# FATSC-DevKit_v10.net
KiCad netlist of a schematic drawn in EAGLE
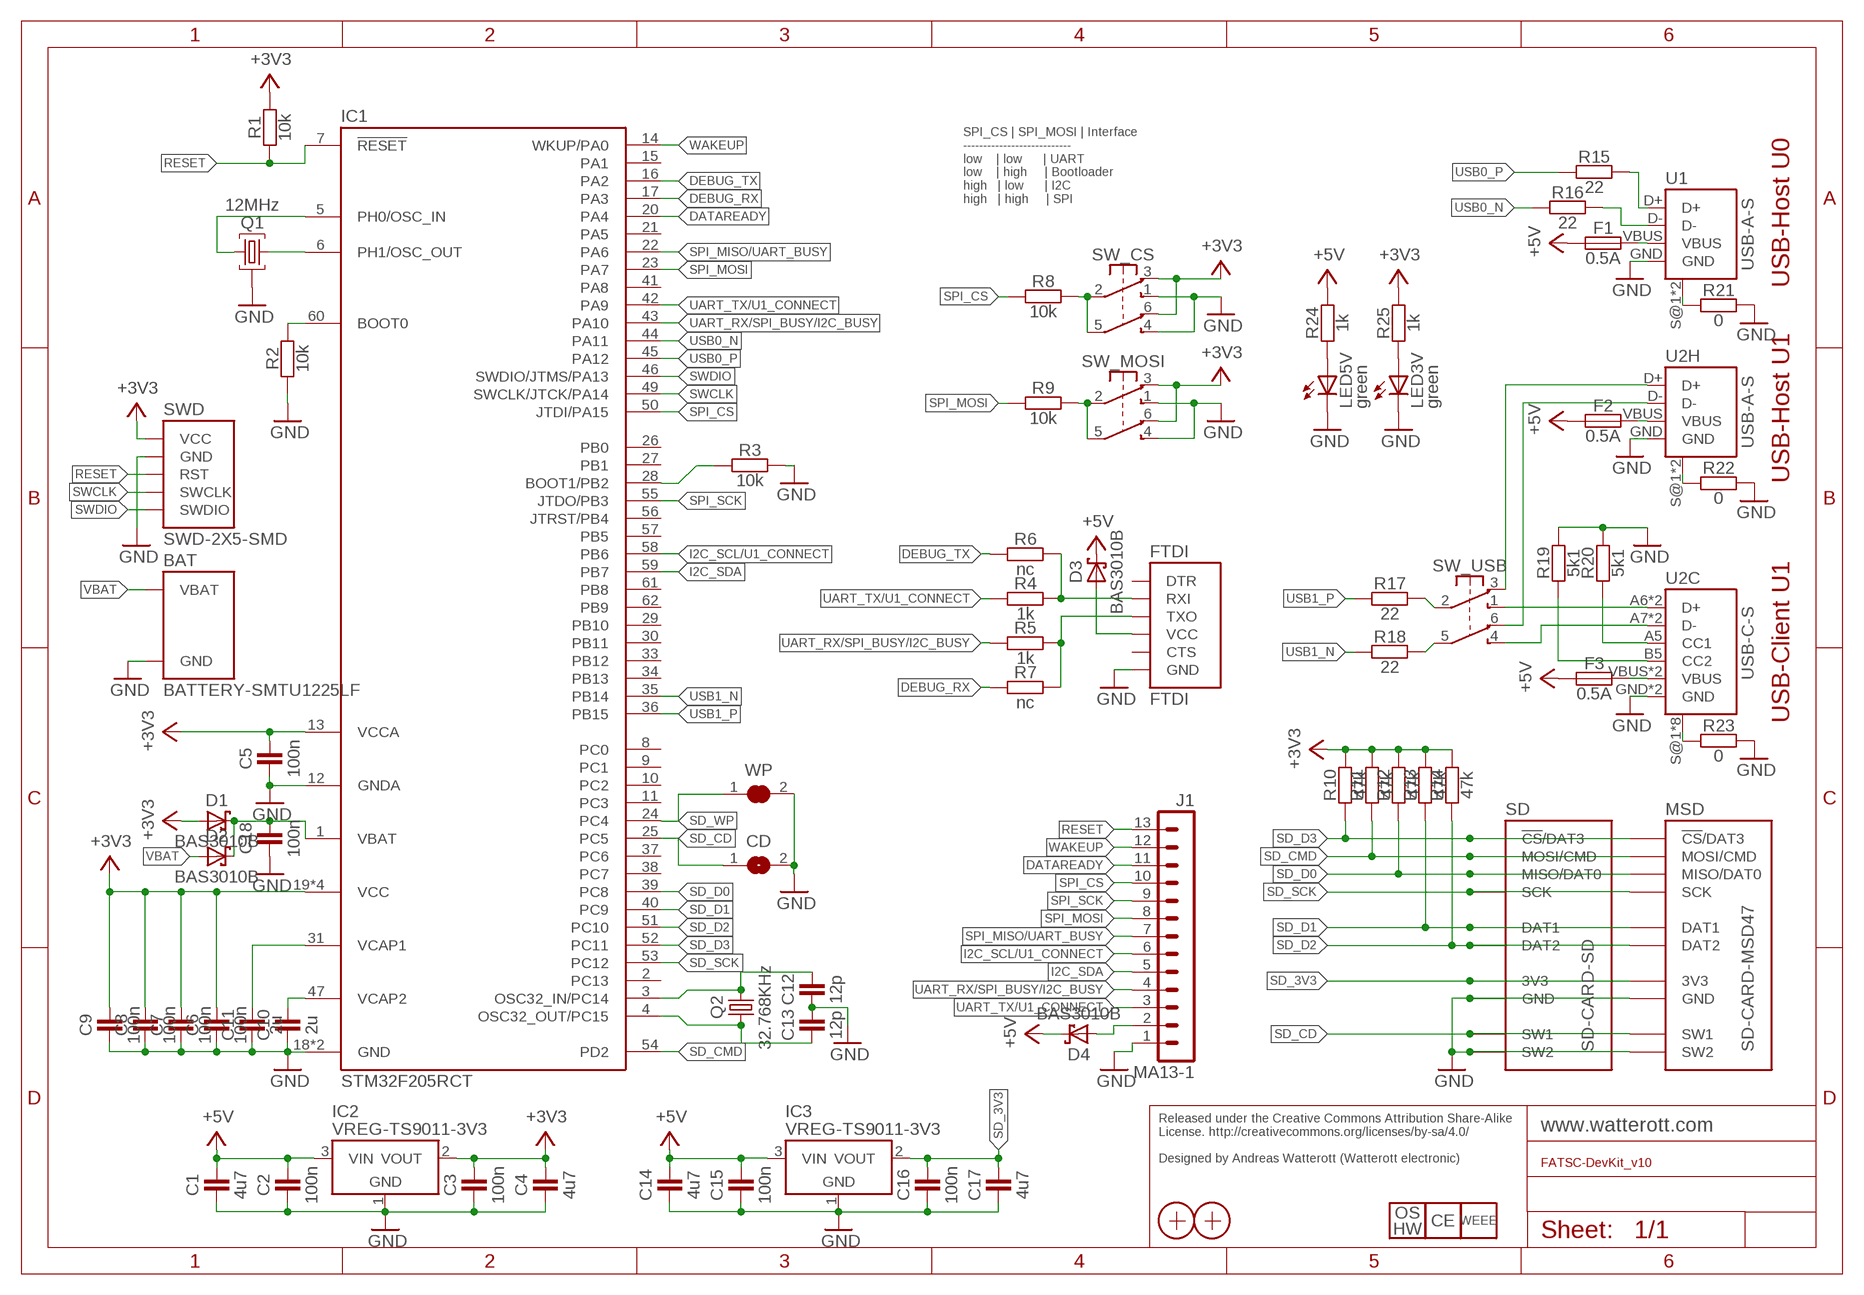
[diagram p0: schematic, sheet 1]

(export (version "E")
  (design (tool "Eeschema 10.0.6"))
  (components
    (comp (ref "BAT")
      (value "BATTERY-SMTU1225LF")
      (footprint "eagle-import:BAT-SMTU1225LF")
      (libsource (lib "eagle-import") (part "BATTERY-SMTU1225LF"))
    )
    (comp (ref "C1")
      (value "4u7")
      (footprint "eagle-import:C0603")
      (libsource (lib "eagle-import") (part "CAPACITOR-0603"))
    )
    (comp (ref "C2")
      (value "100n")
      (footprint "eagle-import:C0603")
      (libsource (lib "eagle-import") (part "CAPACITOR-0603"))
    )
    (comp (ref "C3")
      (value "100n")
      (footprint "eagle-import:C0603")
      (libsource (lib "eagle-import") (part "CAPACITOR-0603"))
    )
    (comp (ref "C4")
      (value "4u7")
      (footprint "eagle-import:C0603")
      (libsource (lib "eagle-import") (part "CAPACITOR-0603"))
    )
    (comp (ref "C5")
      (value "100n")
      (footprint "eagle-import:C0603")
      (libsource (lib "eagle-import") (part "CAPACITOR-0603"))
    )
    (comp (ref "C6")
      (value "100n")
      (footprint "eagle-import:C0603")
      (libsource (lib "eagle-import") (part "CAPACITOR-0603"))
    )
    (comp (ref "C7")
      (value "100n")
      (footprint "eagle-import:C0603")
      (libsource (lib "eagle-import") (part "CAPACITOR-0603"))
    )
    (comp (ref "C8")
      (value "100n")
      (footprint "eagle-import:C0603")
      (libsource (lib "eagle-import") (part "CAPACITOR-0603"))
    )
    (comp (ref "C9")
      (value "100n")
      (footprint "eagle-import:C0603")
      (libsource (lib "eagle-import") (part "CAPACITOR-0603"))
    )
    (comp (ref "C10")
      (value "2u")
      (footprint "eagle-import:C0603")
      (libsource (lib "eagle-import") (part "CAPACITOR-0603"))
    )
    (comp (ref "C11")
      (value "2u")
      (footprint "eagle-import:C0603")
      (libsource (lib "eagle-import") (part "CAPACITOR-0603"))
    )
    (comp (ref "C12")
      (value "12p")
      (footprint "eagle-import:C0603")
      (libsource (lib "eagle-import") (part "CAPACITOR-0603"))
    )
    (comp (ref "C13")
      (value "12p")
      (footprint "eagle-import:C0603")
      (libsource (lib "eagle-import") (part "CAPACITOR-0603"))
    )
    (comp (ref "C14")
      (value "4u7")
      (footprint "eagle-import:C0603")
      (libsource (lib "eagle-import") (part "CAPACITOR-0603"))
    )
    (comp (ref "C15")
      (value "100n")
      (footprint "eagle-import:C0603")
      (libsource (lib "eagle-import") (part "CAPACITOR-0603"))
    )
    (comp (ref "C16")
      (value "100n")
      (footprint "eagle-import:C0603")
      (libsource (lib "eagle-import") (part "CAPACITOR-0603"))
    )
    (comp (ref "C17")
      (value "4u7")
      (footprint "eagle-import:C0603")
      (libsource (lib "eagle-import") (part "CAPACITOR-0603"))
    )
    (comp (ref "C18")
      (value "100n")
      (footprint "eagle-import:C0603")
      (libsource (lib "eagle-import") (part "CAPACITOR-0603"))
    )
    (comp (ref "CD")
      (value "JUMPER2-0603-NC")
      (footprint "eagle-import:JUMPER2-0603_NC")
      (libsource (lib "eagle-import") (part "JUMPER2-0603-NC"))
    )
    (comp (ref "D1")
      (value "BAS3010B")
      (footprint "eagle-import:SOD323")
      (libsource (lib "eagle-import") (part "D_SCHOTTKY-SOD323"))
    )
    (comp (ref "D2")
      (value "BAS3010B")
      (footprint "eagle-import:SOD323")
      (libsource (lib "eagle-import") (part "D_SCHOTTKY-SOD323"))
    )
    (comp (ref "D3")
      (value "BAS3010B")
      (footprint "eagle-import:SOD323")
      (libsource (lib "eagle-import") (part "D_SCHOTTKY-SOD323"))
    )
    (comp (ref "D4")
      (value "BAS3010B")
      (footprint "eagle-import:SOD323")
      (libsource (lib "eagle-import") (part "D_SCHOTTKY-SOD323"))
    )
    (comp (ref "F1")
      (value "0.5A")
      (footprint "eagle-import:C0805")
      (libsource (lib "eagle-import") (part "FUSE-0805"))
    )
    (comp (ref "F2")
      (value "0.5A")
      (footprint "eagle-import:C0805")
      (libsource (lib "eagle-import") (part "FUSE-0805"))
    )
    (comp (ref "F3")
      (value "0.5A")
      (footprint "eagle-import:C0805")
      (libsource (lib "eagle-import") (part "FUSE-0805"))
    )
    (comp (ref "FTDI")
      (value "FTDI")
      (footprint "eagle-import:FTDI")
      (libsource (lib "eagle-import") (part "FTDI"))
    )
    (comp (ref "IC1")
      (value "STM32F205RCT")
      (footprint "eagle-import:LQFP64")
      (libsource (lib "eagle-import") (part "STM32F205RCT"))
    )
    (comp (ref "IC2")
      (value "VREG-TS9011-3V3")
      (footprint "eagle-import:SOT23")
      (libsource (lib "eagle-import") (part "VREG-TS9011-3V3"))
    )
    (comp (ref "IC3")
      (value "VREG-TS9011-3V3")
      (footprint "eagle-import:SOT23")
      (libsource (lib "eagle-import") (part "VREG-TS9011-3V3"))
    )
    (comp (ref "J1")
      (value "MA13-1")
      (footprint "eagle-import:MA13-1")
      (libsource (lib "eagle-import") (part "MA13-1"))
    )
    (comp (ref "LED3V")
      (value "green")
      (footprint "eagle-import:C0603")
      (libsource (lib "eagle-import") (part "LED-0603"))
    )
    (comp (ref "LED5V")
      (value "green")
      (footprint "eagle-import:C0603")
      (libsource (lib "eagle-import") (part "LED-0603"))
    )
    (comp (ref "LOGO7")
      (value "LOGO_OSHW-4")
      (footprint "eagle-import:OSHW_4MM")
      (libsource (lib "eagle-import") (part "LOGO_OSHW-4"))
    )
    (comp (ref "LOGO8")
      (value "LOGO_CE-2")
      (footprint "eagle-import:CE_2MM")
      (libsource (lib "eagle-import") (part "LOGO_CE-2"))
    )
    (comp (ref "LOGO9")
      (value "LOGO_WEEE-4")
      (footprint "eagle-import:WEEE_4MM")
      (libsource (lib "eagle-import") (part "LOGO_WEEE-4"))
    )
    (comp (ref "MSD")
      (value "SD-CARD-MSD47")
      (footprint "eagle-import:SD_47309XXXX")
      (libsource (lib "eagle-import") (part "SD-CARD-MSD47"))
    )
    (comp (ref "Q1")
      (value "12MHz")
      (footprint "eagle-import:CRYSTAL_32X13")
      (libsource (lib "eagle-import") (part "CRYSTAL-RES-32"))
    )
    (comp (ref "Q2")
      (value "32.768KHz")
      (footprint "eagle-import:CRYSTAL_ZM315")
      (libsource (lib "eagle-import") (part "CRYSTAL-ZM315"))
    )
    (comp (ref "R1")
      (value "10k")
      (footprint "eagle-import:C0603")
      (libsource (lib "eagle-import") (part "RESISTOR-0603"))
    )
    (comp (ref "R2")
      (value "10k")
      (footprint "eagle-import:C0603")
      (libsource (lib "eagle-import") (part "RESISTOR-0603"))
    )
    (comp (ref "R3")
      (value "10k")
      (footprint "eagle-import:C0603")
      (libsource (lib "eagle-import") (part "RESISTOR-0603"))
    )
    (comp (ref "R4")
      (value "1k")
      (footprint "eagle-import:C0603")
      (libsource (lib "eagle-import") (part "RESISTOR-0603"))
    )
    (comp (ref "R5")
      (value "1k")
      (footprint "eagle-import:C0603")
      (libsource (lib "eagle-import") (part "RESISTOR-0603"))
    )
    (comp (ref "R6")
      (value "nc")
      (footprint "eagle-import:C0603")
      (libsource (lib "eagle-import") (part "RESISTOR-0603"))
    )
    (comp (ref "R7")
      (value "nc")
      (footprint "eagle-import:C0603")
      (libsource (lib "eagle-import") (part "RESISTOR-0603"))
    )
    (comp (ref "R8")
      (value "10k")
      (footprint "eagle-import:C0603")
      (libsource (lib "eagle-import") (part "RESISTOR-0603"))
    )
    (comp (ref "R9")
      (value "10k")
      (footprint "eagle-import:C0603")
      (libsource (lib "eagle-import") (part "RESISTOR-0603"))
    )
    (comp (ref "R10")
      (value "47k")
      (footprint "eagle-import:C0603")
      (libsource (lib "eagle-import") (part "RESISTOR-0603"))
    )
    (comp (ref "R11")
      (value "47k")
      (footprint "eagle-import:C0603")
      (libsource (lib "eagle-import") (part "RESISTOR-0603"))
    )
    (comp (ref "R12")
      (value "47k")
      (footprint "eagle-import:C0603")
      (libsource (lib "eagle-import") (part "RESISTOR-0603"))
    )
    (comp (ref "R13")
      (value "47k")
      (footprint "eagle-import:C0603")
      (libsource (lib "eagle-import") (part "RESISTOR-0603"))
    )
    (comp (ref "R14")
      (value "47k")
      (footprint "eagle-import:C0603")
      (libsource (lib "eagle-import") (part "RESISTOR-0603"))
    )
    (comp (ref "R15")
      (value "22")
      (footprint "eagle-import:C0603")
      (libsource (lib "eagle-import") (part "RESISTOR-0603"))
    )
    (comp (ref "R16")
      (value "22")
      (footprint "eagle-import:C0603")
      (libsource (lib "eagle-import") (part "RESISTOR-0603"))
    )
    (comp (ref "R17")
      (value "22")
      (footprint "eagle-import:C0603")
      (libsource (lib "eagle-import") (part "RESISTOR-0603"))
    )
    (comp (ref "R18")
      (value "22")
      (footprint "eagle-import:C0603")
      (libsource (lib "eagle-import") (part "RESISTOR-0603"))
    )
    (comp (ref "R19")
      (value "5k1")
      (footprint "eagle-import:C0603")
      (libsource (lib "eagle-import") (part "RESISTOR-0603"))
    )
    (comp (ref "R20")
      (value "5k1")
      (footprint "eagle-import:C0603")
      (libsource (lib "eagle-import") (part "RESISTOR-0603"))
    )
    (comp (ref "R21")
      (value "0")
      (footprint "eagle-import:C0603")
      (libsource (lib "eagle-import") (part "RESISTOR-0603"))
    )
    (comp (ref "R22")
      (value "0")
      (footprint "eagle-import:C0603")
      (libsource (lib "eagle-import") (part "RESISTOR-0603"))
    )
    (comp (ref "R23")
      (value "0")
      (footprint "eagle-import:C0603")
      (libsource (lib "eagle-import") (part "RESISTOR-0603"))
    )
    (comp (ref "R24")
      (value "1k")
      (footprint "eagle-import:C0603")
      (libsource (lib "eagle-import") (part "RESISTOR-0603"))
    )
    (comp (ref "R25")
      (value "1k")
      (footprint "eagle-import:C0603")
      (libsource (lib "eagle-import") (part "RESISTOR-0603"))
    )
    (comp (ref "SD")
      (value "SD-CARD-SD")
      (footprint "eagle-import:SD_SDBMF00915B0T2")
      (libsource (lib "eagle-import") (part "SD-CARD-SD"))
    )
    (comp (ref "SWD")
      (value "SWD-2X5-SMD")
      (footprint "eagle-import:SWD-2X5_SMD")
      (libsource (lib "eagle-import") (part "SWD-2X5-SMD"))
    )
    (comp (ref "SW_CS")
      (value "SW-2UM-CUS22B")
      (footprint "eagle-import:CUS22B")
      (libsource (lib "eagle-import") (part "SW-2UM-CUS22B"))
    )
    (comp (ref "SW_MOSI")
      (value "SW-2UM-CUS22B")
      (footprint "eagle-import:CUS22B")
      (libsource (lib "eagle-import") (part "SW-2UM-CUS22B"))
    )
    (comp (ref "SW_USB")
      (value "SW-2UM-CUS22B")
      (footprint "eagle-import:CUS22B")
      (libsource (lib "eagle-import") (part "SW-2UM-CUS22B"))
    )
    (comp (ref "U1")
      (value "USB-A-S")
      (footprint "eagle-import:USB-A-S")
      (libsource (lib "eagle-import") (part "USB-A-S"))
    )
    (comp (ref "U2C")
      (value "USB-C-S")
      (footprint "eagle-import:USB-C-S")
      (libsource (lib "eagle-import") (part "USB-C-S"))
    )
    (comp (ref "U2H")
      (value "USB-A-S")
      (footprint "eagle-import:USB-A-S")
      (libsource (lib "eagle-import") (part "USB-A-S"))
    )
    (comp (ref "WP")
      (value "JUMPER2-0603")
      (footprint "eagle-import:JUMPER2-0603")
      (libsource (lib "eagle-import") (part "JUMPER2-0603"))
    )
    (comp (ref "X1")
      (value "PASSER-07")
      (footprint "eagle-import:PASSER_07MM")
      (libsource (lib "eagle-import") (part "PASSER-07"))
    )
    (comp (ref "X2")
      (value "PASSER-07")
      (footprint "eagle-import:PASSER_07MM")
      (libsource (lib "eagle-import") (part "PASSER-07"))
    )
  )
  (nets
    (net (code "1") (name "+3V3") (class "Default")
      (node (ref "C3") (pin "2") (pinfunction "2_2") (pintype "passive"))
      (node (ref "C4") (pin "2") (pinfunction "2_2") (pintype "passive"))
      (node (ref "C5") (pin "2") (pinfunction "2_2") (pintype "passive"))
      (node (ref "C6") (pin "2") (pinfunction "2_2") (pintype "passive"))
      (node (ref "C7") (pin "2") (pinfunction "2_2") (pintype "passive"))
      (node (ref "C8") (pin "2") (pinfunction "2_2") (pintype "passive"))
      (node (ref "C9") (pin "2") (pinfunction "2_2") (pintype "passive"))
      (node (ref "D1") (pin "A") (pinfunction "A_A") (pintype "passive"))
      (node (ref "IC1") (pin "13") (pinfunction "VCCA_13") (pintype "power_in"))
      (node (ref "IC1") (pin "19") (pinfunction "VCC_19") (pintype "power_in"))
      (node (ref "IC1") (pin "32") (pinfunction "VCC_32") (pintype "power_in"))
      (node (ref "IC1") (pin "48") (pinfunction "VCC_48") (pintype "power_in"))
      (node (ref "IC1") (pin "64") (pinfunction "VCC_64") (pintype "power_in"))
      (node (ref "IC2") (pin "2") (pinfunction "VOUT_2") (pintype "power_in"))
      (node (ref "R1") (pin "2") (pinfunction "2_2") (pintype "passive"))
      (node (ref "R10") (pin "2") (pinfunction "2_2") (pintype "passive"))
      (node (ref "R11") (pin "2") (pinfunction "2_2") (pintype "passive"))
      (node (ref "R12") (pin "2") (pinfunction "2_2") (pintype "passive"))
      (node (ref "R13") (pin "2") (pinfunction "2_2") (pintype "passive"))
      (node (ref "R14") (pin "2") (pinfunction "2_2") (pintype "passive"))
      (node (ref "R25") (pin "2") (pinfunction "2_2") (pintype "passive"))
      (node (ref "SWD") (pin "VCC") (pinfunction "VCC_VCC") (pintype "power_in"))
      (node (ref "SW_CS") (pin "3") (pinfunction "NC1_3") (pintype "passive"))
      (node (ref "SW_CS") (pin "6") (pinfunction "NC2_6") (pintype "passive"))
      (node (ref "SW_MOSI") (pin "3") (pinfunction "NC1_3") (pintype "passive"))
      (node (ref "SW_MOSI") (pin "6") (pinfunction "NC2_6") (pintype "passive"))
    )
    (net (code "2") (name "+5V") (class "Default")
      (node (ref "C1") (pin "2") (pinfunction "2_2") (pintype "passive"))
      (node (ref "C14") (pin "2") (pinfunction "2_2") (pintype "passive"))
      (node (ref "C15") (pin "2") (pinfunction "2_2") (pintype "passive"))
      (node (ref "C2") (pin "2") (pinfunction "2_2") (pintype "passive"))
      (node (ref "D3") (pin "C") (pinfunction "C_C") (pintype "passive"))
      (node (ref "D4") (pin "C") (pinfunction "C_C") (pintype "passive"))
      (node (ref "F1") (pin "1") (pinfunction "1_1") (pintype "passive"))
      (node (ref "F2") (pin "1") (pinfunction "1_1") (pintype "passive"))
      (node (ref "F3") (pin "1") (pinfunction "1_1") (pintype "passive"))
      (node (ref "IC2") (pin "3") (pinfunction "VIN_3") (pintype "power_in"))
      (node (ref "IC3") (pin "3") (pinfunction "VIN_3") (pintype "power_in"))
      (node (ref "R24") (pin "2") (pinfunction "2_2") (pintype "passive"))
    )
    (net (code "3") (name "DATAREADY") (class "Default")
      (node (ref "IC1") (pin "20") (pinfunction "PA4_20") (pintype "bidirectional"))
      (node (ref "J1") (pin "11") (pinfunction "11_11") (pintype "passive"))
    )
    (net (code "4") (name "DEBUG_RX") (class "Default")
      (node (ref "IC1") (pin "17") (pinfunction "PA3_17") (pintype "bidirectional"))
      (node (ref "R7") (pin "1") (pinfunction "1_1") (pintype "passive"))
    )
    (net (code "5") (name "DEBUG_TX") (class "Default")
      (node (ref "IC1") (pin "16") (pinfunction "PA2_16") (pintype "bidirectional"))
      (node (ref "R6") (pin "1") (pinfunction "1_1") (pintype "passive"))
    )
    (net (code "6") (name "GND") (class "Default")
      (node (ref "BAT") (pin "-") (pinfunction "GND_-") (pintype "power_in"))
      (node (ref "C1") (pin "1") (pinfunction "1_1") (pintype "passive"))
      (node (ref "C10") (pin "1") (pinfunction "1_1") (pintype "passive"))
      (node (ref "C11") (pin "1") (pinfunction "1_1") (pintype "passive"))
      (node (ref "C12") (pin "1") (pinfunction "1_1") (pintype "passive"))
      (node (ref "C13") (pin "2") (pinfunction "2_2") (pintype "passive"))
      (node (ref "C14") (pin "1") (pinfunction "1_1") (pintype "passive"))
      (node (ref "C15") (pin "1") (pinfunction "1_1") (pintype "passive"))
      (node (ref "C16") (pin "1") (pinfunction "1_1") (pintype "passive"))
      (node (ref "C17") (pin "1") (pinfunction "1_1") (pintype "passive"))
      (node (ref "C18") (pin "1") (pinfunction "1_1") (pintype "passive"))
      (node (ref "C2") (pin "1") (pinfunction "1_1") (pintype "passive"))
      (node (ref "C3") (pin "1") (pinfunction "1_1") (pintype "passive"))
      (node (ref "C4") (pin "1") (pinfunction "1_1") (pintype "passive"))
      (node (ref "C5") (pin "1") (pinfunction "1_1") (pintype "passive"))
      (node (ref "C6") (pin "1") (pinfunction "1_1") (pintype "passive"))
      (node (ref "C7") (pin "1") (pinfunction "1_1") (pintype "passive"))
      (node (ref "C8") (pin "1") (pinfunction "1_1") (pintype "passive"))
      (node (ref "C9") (pin "1") (pinfunction "1_1") (pintype "passive"))
      (node (ref "CD") (pin "2") (pinfunction "2_2") (pintype "passive"))
      (node (ref "FTDI") (pin "1-GND") (pinfunction "GND_1-GND") (pintype "power_in"))
      (node (ref "IC1") (pin "12") (pinfunction "GNDA_12") (pintype "power_in"))
      (node (ref "IC1") (pin "18") (pinfunction "GND_18") (pintype "power_in"))
      (node (ref "IC1") (pin "63") (pinfunction "GND_63") (pintype "power_in"))
      (node (ref "IC2") (pin "1") (pinfunction "GND_1") (pintype "power_in"))
      (node (ref "IC3") (pin "1") (pinfunction "GND_1") (pintype "power_in"))
      (node (ref "J1") (pin "1") (pinfunction "1_1") (pintype "passive"))
      (node (ref "LED3V") (pin "C") (pinfunction "C_C") (pintype "passive"))
      (node (ref "LED5V") (pin "C") (pinfunction "C_C") (pintype "passive"))
      (node (ref "MSD") (pin "GND") (pinfunction "GND_GND") (pintype "bidirectional"))
      (node (ref "MSD") (pin "GND@1") (pinfunction "GND_GND@1") (pintype "bidirectional"))
      (node (ref "MSD") (pin "GND@2") (pinfunction "GND_GND@2") (pintype "bidirectional"))
      (node (ref "MSD") (pin "SW2") (pinfunction "SW2_SW2") (pintype "bidirectional"))
      (node (ref "Q1") (pin "GND") (pinfunction "GND_GND") (pintype "passive"))
      (node (ref "R19") (pin "2") (pinfunction "2_2") (pintype "passive"))
      (node (ref "R2") (pin "1") (pinfunction "1_1") (pintype "passive"))
      (node (ref "R20") (pin "2") (pinfunction "2_2") (pintype "passive"))
      (node (ref "R21") (pin "2") (pinfunction "2_2") (pintype "passive"))
      (node (ref "R22") (pin "2") (pinfunction "2_2") (pintype "passive"))
      (node (ref "R23") (pin "2") (pinfunction "2_2") (pintype "passive"))
      (node (ref "R3") (pin "2") (pinfunction "2_2") (pintype "passive"))
      (node (ref "SD") (pin "GND@1") (pinfunction "GND_GND@1") (pintype "bidirectional"))
      (node (ref "SD") (pin "GND@2") (pinfunction "GND_GND@2") (pintype "bidirectional"))
      (node (ref "SD") (pin "GND@3") (pinfunction "GND_GND@3") (pintype "bidirectional"))
      (node (ref "SD") (pin "SW2") (pinfunction "SW2_SW2") (pintype "bidirectional"))
      (node (ref "SWD") (pin "GND@1") (pinfunction "GND_GND@1") (pintype "power_in"))
      (node (ref "SWD") (pin "GND@2") (pinfunction "GND_GND@2") (pintype "power_in"))
      (node (ref "SWD") (pin "GND@3") (pinfunction "GND_GND@3") (pintype "power_in"))
      (node (ref "SW_CS") (pin "1") (pinfunction "NO1_1") (pintype "passive"))
      (node (ref "SW_CS") (pin "4") (pinfunction "NO2_4") (pintype "passive"))
      (node (ref "SW_MOSI") (pin "1") (pinfunction "NO1_1") (pintype "passive"))
      (node (ref "SW_MOSI") (pin "4") (pinfunction "NO2_4") (pintype "passive"))
      (node (ref "U1") (pin "GND") (pinfunction "GND_GND") (pintype "power_in"))
      (node (ref "U2C") (pin "GND") (pinfunction "GND_GND") (pintype "power_in"))
      (node (ref "U2C") (pin "GND2") (pinfunction "GND_GND2") (pintype "power_in"))
      (node (ref "U2H") (pin "GND") (pinfunction "GND_GND") (pintype "power_in"))
      (node (ref "WP") (pin "2") (pinfunction "2_2") (pintype "passive"))
    )
    (net (code "7") (name "I2C_SCL{slash}U1_CONNECT") (class "Default")
      (node (ref "IC1") (pin "58") (pinfunction "PB6_58") (pintype "bidirectional"))
      (node (ref "J1") (pin "6") (pinfunction "6_6") (pintype "passive"))
    )
    (net (code "8") (name "I2C_SDA") (class "Default")
      (node (ref "IC1") (pin "59") (pinfunction "PB7_59") (pintype "bidirectional"))
      (node (ref "J1") (pin "5") (pinfunction "5_5") (pintype "passive"))
    )
    (net (code "9") (name "Net-(D4-PadA)") (class "Default")
      (node (ref "D4") (pin "A") (pinfunction "A_A") (pintype "passive"))
      (node (ref "J1") (pin "2") (pinfunction "2_2") (pintype "passive"))
    )
    (net (code "10") (name "Net-(F1-Pad2)") (class "Default")
      (node (ref "F1") (pin "2") (pinfunction "2_2") (pintype "passive"))
      (node (ref "U1") (pin "VBUS") (pinfunction "VBUS_VBUS") (pintype "power_in"))
    )
    (net (code "11") (name "Net-(F2-Pad2)") (class "Default")
      (node (ref "F2") (pin "2") (pinfunction "2_2") (pintype "passive"))
      (node (ref "U2H") (pin "VBUS") (pinfunction "VBUS_VBUS") (pintype "power_in"))
    )
    (net (code "12") (name "Net-(F3-Pad2)") (class "Default")
      (node (ref "F3") (pin "2") (pinfunction "2_2") (pintype "passive"))
      (node (ref "U2C") (pin "VBUS") (pinfunction "VBUS_VBUS") (pintype "power_in"))
      (node (ref "U2C") (pin "VBUS2") (pinfunction "VBUS_VBUS2") (pintype "power_in"))
    )
    (net (code "13") (name "Net-(FTDI-RXI)") (class "Default")
      (node (ref "FTDI") (pin "5-RXI") (pinfunction "RXI_5-RXI") (pintype "bidirectional"))
      (node (ref "R4") (pin "2") (pinfunction "2_2") (pintype "passive"))
      (node (ref "R6") (pin "2") (pinfunction "2_2") (pintype "passive"))
    )
    (net (code "14") (name "Net-(FTDI-TXO)") (class "Default")
      (node (ref "FTDI") (pin "4-TXO") (pinfunction "TXO_4-TXO") (pintype "bidirectional"))
      (node (ref "R5") (pin "2") (pinfunction "2_2") (pintype "passive"))
      (node (ref "R7") (pin "2") (pinfunction "2_2") (pintype "passive"))
    )
    (net (code "15") (name "Net-(FTDI-VCC)") (class "Default")
      (node (ref "D3") (pin "A") (pinfunction "A_A") (pintype "passive"))
      (node (ref "FTDI") (pin "3-VCC") (pinfunction "VCC_3-VCC") (pintype "power_in"))
    )
    (net (code "16") (name "Net-(IC1-BOOT0)") (class "Default")
      (node (ref "IC1") (pin "60") (pinfunction "BOOT0_60") (pintype "bidirectional"))
      (node (ref "R2") (pin "2") (pinfunction "2_2") (pintype "passive"))
    )
    (net (code "17") (name "Net-(IC1-BOOT1{slash}PB2)") (class "Default")
      (node (ref "IC1") (pin "28") (pinfunction "BOOT1/PB2_28") (pintype "bidirectional"))
      (node (ref "R3") (pin "1") (pinfunction "1_1") (pintype "passive"))
    )
    (net (code "18") (name "Net-(IC1-OSC32_IN{slash}PC14)") (class "Default")
      (node (ref "C12") (pin "2") (pinfunction "2_2") (pintype "passive"))
      (node (ref "IC1") (pin "3") (pinfunction "OSC32_IN/PC14_3") (pintype "bidirectional"))
      (node (ref "Q2") (pin "2") (pinfunction "2_2") (pintype "passive"))
    )
    (net (code "19") (name "Net-(IC1-OSC32_OUT{slash}PC15)") (class "Default")
      (node (ref "C13") (pin "1") (pinfunction "1_1") (pintype "passive"))
      (node (ref "IC1") (pin "4") (pinfunction "OSC32_OUT/PC15_4") (pintype "bidirectional"))
      (node (ref "Q2") (pin "1") (pinfunction "1_1") (pintype "passive"))
    )
    (net (code "20") (name "Net-(IC1-PH0{slash}OSC_IN)") (class "Default")
      (node (ref "IC1") (pin "5") (pinfunction "PH0/OSC_IN_5") (pintype "bidirectional"))
      (node (ref "Q1") (pin "2") (pinfunction "2_2") (pintype "passive"))
    )
    (net (code "21") (name "Net-(IC1-PH1{slash}OSC_OUT)") (class "Default")
      (node (ref "IC1") (pin "6") (pinfunction "PH1/OSC_OUT_6") (pintype "bidirectional"))
      (node (ref "Q1") (pin "1") (pinfunction "1_1") (pintype "passive"))
    )
    (net (code "22") (name "Net-(IC1-VBAT)") (class "Default")
      (node (ref "C18") (pin "2") (pinfunction "2_2") (pintype "passive"))
      (node (ref "D1") (pin "C") (pinfunction "C_C") (pintype "passive"))
      (node (ref "D2") (pin "C") (pinfunction "C_C") (pintype "passive"))
      (node (ref "IC1") (pin "1") (pinfunction "VBAT_1") (pintype "power_in"))
    )
    (net (code "23") (name "Net-(IC1-VCAP1)") (class "Default")
      (node (ref "C11") (pin "2") (pinfunction "2_2") (pintype "passive"))
      (node (ref "IC1") (pin "31") (pinfunction "VCAP1_31") (pintype "power_in"))
    )
    (net (code "24") (name "Net-(IC1-VCAP2)") (class "Default")
      (node (ref "C10") (pin "2") (pinfunction "2_2") (pintype "passive"))
      (node (ref "IC1") (pin "47") (pinfunction "VCAP2_47") (pintype "power_in"))
    )
    (net (code "25") (name "Net-(LED3V-PadA)") (class "Default")
      (node (ref "LED3V") (pin "A") (pinfunction "A_A") (pintype "passive"))
      (node (ref "R25") (pin "1") (pinfunction "1_1") (pintype "passive"))
    )
    (net (code "26") (name "Net-(LED5V-PadA)") (class "Default")
      (node (ref "LED5V") (pin "A") (pinfunction "A_A") (pintype "passive"))
      (node (ref "R24") (pin "1") (pinfunction "1_1") (pintype "passive"))
    )
    (net (code "27") (name "Net-(R15-Pad2)") (class "Default")
      (node (ref "R15") (pin "2") (pinfunction "2_2") (pintype "passive"))
      (node (ref "U1") (pin "D+") (pinfunction "D+_D+") (pintype "bidirectional"))
    )
    (net (code "28") (name "Net-(R16-Pad2)") (class "Default")
      (node (ref "R16") (pin "2") (pinfunction "2_2") (pintype "passive"))
      (node (ref "U1") (pin "D-") (pinfunction "D-_D-") (pintype "bidirectional"))
    )
    (net (code "29") (name "Net-(R21-Pad1)") (class "Default")
      (node (ref "R21") (pin "1") (pinfunction "1_1") (pintype "passive"))
      (node (ref "U1") (pin "S@1") (pinfunction "SHIELD_S@1") (pintype "passive"))
      (node (ref "U1") (pin "S@2") (pinfunction "SHIELD_S@2") (pintype "passive"))
    )
    (net (code "30") (name "Net-(R22-Pad1)") (class "Default")
      (node (ref "R22") (pin "1") (pinfunction "1_1") (pintype "passive"))
      (node (ref "U2H") (pin "S@1") (pinfunction "SHIELD_S@1") (pintype "passive"))
      (node (ref "U2H") (pin "S@2") (pinfunction "SHIELD_S@2") (pintype "passive"))
    )
    (net (code "31") (name "Net-(R23-Pad1)") (class "Default")
      (node (ref "R23") (pin "1") (pinfunction "1_1") (pintype "passive"))
      (node (ref "U2C") (pin "S@1") (pinfunction "SHIELD_S@1") (pintype "passive"))
      (node (ref "U2C") (pin "S@2") (pinfunction "SHIELD_S@2") (pintype "passive"))
      (node (ref "U2C") (pin "S@3") (pinfunction "SHIELD_S@3") (pintype "passive"))
      (node (ref "U2C") (pin "S@4") (pinfunction "SHIELD_S@4") (pintype "passive"))
      (node (ref "U2C") (pin "S@5") (pinfunction "SHIELD_S@5") (pintype "passive"))
      (node (ref "U2C") (pin "S@6") (pinfunction "SHIELD_S@6") (pintype "passive"))
      (node (ref "U2C") (pin "S@7") (pinfunction "SHIELD_S@7") (pintype "passive"))
      (node (ref "U2C") (pin "S@8") (pinfunction "SHIELD_S@8") (pintype "passive"))
    )
    (net (code "32") (name "Net-(SW_CS-C1)") (class "Default")
      (node (ref "R8") (pin "2") (pinfunction "2_2") (pintype "passive"))
      (node (ref "SW_CS") (pin "2") (pinfunction "C1_2") (pintype "passive"))
      (node (ref "SW_CS") (pin "5") (pinfunction "C2_5") (pintype "passive"))
    )
    (net (code "33") (name "Net-(SW_MOSI-C1)") (class "Default")
      (node (ref "R9") (pin "2") (pinfunction "2_2") (pintype "passive"))
      (node (ref "SW_MOSI") (pin "2") (pinfunction "C1_2") (pintype "passive"))
      (node (ref "SW_MOSI") (pin "5") (pinfunction "C2_5") (pintype "passive"))
    )
    (net (code "34") (name "Net-(SW_USB-C1)") (class "Default")
      (node (ref "R17") (pin "2") (pinfunction "2_2") (pintype "passive"))
      (node (ref "SW_USB") (pin "2") (pinfunction "C1_2") (pintype "passive"))
    )
    (net (code "35") (name "Net-(SW_USB-C2)") (class "Default")
      (node (ref "R18") (pin "2") (pinfunction "2_2") (pintype "passive"))
      (node (ref "SW_USB") (pin "5") (pinfunction "C2_5") (pintype "passive"))
    )
    (net (code "36") (name "Net-(SW_USB-NC1)") (class "Default")
      (node (ref "SW_USB") (pin "3") (pinfunction "NC1_3") (pintype "passive"))
      (node (ref "U2H") (pin "D+") (pinfunction "D+_D+") (pintype "bidirectional"))
    )
    (net (code "37") (name "Net-(SW_USB-NC2)") (class "Default")
      (node (ref "SW_USB") (pin "6") (pinfunction "NC2_6") (pintype "passive"))
      (node (ref "U2H") (pin "D-") (pinfunction "D-_D-") (pintype "bidirectional"))
    )
    (net (code "38") (name "Net-(SW_USB-NO1)") (class "Default")
      (node (ref "SW_USB") (pin "1") (pinfunction "NO1_1") (pintype "passive"))
      (node (ref "U2C") (pin "A6") (pinfunction "D+_A6") (pintype "bidirectional"))
      (node (ref "U2C") (pin "B6") (pinfunction "D+_B6") (pintype "bidirectional"))
    )
    (net (code "39") (name "Net-(SW_USB-NO2)") (class "Default")
      (node (ref "SW_USB") (pin "4") (pinfunction "NO2_4") (pintype "passive"))
      (node (ref "U2C") (pin "A7") (pinfunction "D-_A7") (pintype "bidirectional"))
      (node (ref "U2C") (pin "B7") (pinfunction "D-_B7") (pintype "bidirectional"))
    )
    (net (code "40") (name "Net-(U2C-CC1)") (class "Default")
      (node (ref "R20") (pin "1") (pinfunction "1_1") (pintype "passive"))
      (node (ref "U2C") (pin "A5") (pinfunction "CC1_A5") (pintype "bidirectional"))
    )
    (net (code "41") (name "Net-(U2C-CC2)") (class "Default")
      (node (ref "R19") (pin "1") (pinfunction "1_1") (pintype "passive"))
      (node (ref "U2C") (pin "B5") (pinfunction "CC2_B5") (pintype "bidirectional"))
    )
    (net (code "42") (name "RESET") (class "Default")
      (node (ref "IC1") (pin "7") (pinfunction "~{RESET}_7") (pintype "input"))
      (node (ref "J1") (pin "13") (pinfunction "13_13") (pintype "passive"))
      (node (ref "R1") (pin "1") (pinfunction "1_1") (pintype "passive"))
      (node (ref "SWD") (pin "RST") (pinfunction "RST_RST") (pintype "bidirectional"))
    )
    (net (code "43") (name "SD_3V3") (class "Default")
      (node (ref "C16") (pin "2") (pinfunction "2_2") (pintype "passive"))
      (node (ref "C17") (pin "2") (pinfunction "2_2") (pintype "passive"))
      (node (ref "IC3") (pin "2") (pinfunction "VOUT_2") (pintype "power_in"))
      (node (ref "MSD") (pin "VCC") (pinfunction "3V3_VCC") (pintype "bidirectional"))
      (node (ref "SD") (pin "VCC") (pinfunction "3V3_VCC") (pintype "bidirectional"))
    )
    (net (code "44") (name "SD_CD") (class "Default")
      (node (ref "CD") (pin "1") (pinfunction "1_1") (pintype "passive"))
      (node (ref "IC1") (pin "25") (pinfunction "PC5_25") (pintype "bidirectional"))
      (node (ref "MSD") (pin "SW1") (pinfunction "SW1_SW1") (pintype "bidirectional"))
      (node (ref "SD") (pin "SW1") (pinfunction "SW1_SW1") (pintype "bidirectional"))
    )
    (net (code "45") (name "SD_CMD") (class "Default")
      (node (ref "IC1") (pin "54") (pinfunction "PD2_54") (pintype "bidirectional"))
      (node (ref "MSD") (pin "MOSI") (pinfunction "MOSI/CMD_MOSI") (pintype "bidirectional"))
      (node (ref "R11") (pin "1") (pinfunction "1_1") (pintype "passive"))
      (node (ref "SD") (pin "MOSI") (pinfunction "MOSI/CMD_MOSI") (pintype "bidirectional"))
    )
    (net (code "46") (name "SD_D0") (class "Default")
      (node (ref "IC1") (pin "39") (pinfunction "PC8_39") (pintype "bidirectional"))
      (node (ref "MSD") (pin "MISO") (pinfunction "MISO/DAT0_MISO") (pintype "bidirectional"))
      (node (ref "R12") (pin "1") (pinfunction "1_1") (pintype "passive"))
      (node (ref "SD") (pin "MISO") (pinfunction "MISO/DAT0_MISO") (pintype "bidirectional"))
    )
    (net (code "47") (name "SD_D1") (class "Default")
      (node (ref "IC1") (pin "40") (pinfunction "PC9_40") (pintype "bidirectional"))
      (node (ref "MSD") (pin "DAT1") (pinfunction "DAT1_DAT1") (pintype "bidirectional"))
      (node (ref "R13") (pin "1") (pinfunction "1_1") (pintype "passive"))
      (node (ref "SD") (pin "DAT1") (pinfunction "DAT1_DAT1") (pintype "bidirectional"))
    )
    (net (code "48") (name "SD_D2") (class "Default")
      (node (ref "IC1") (pin "51") (pinfunction "PC10_51") (pintype "bidirectional"))
      (node (ref "MSD") (pin "DAT2") (pinfunction "DAT2_DAT2") (pintype "bidirectional"))
      (node (ref "R14") (pin "1") (pinfunction "1_1") (pintype "passive"))
      (node (ref "SD") (pin "DAT2") (pinfunction "DAT2_DAT2") (pintype "bidirectional"))
    )
    (net (code "49") (name "SD_D3") (class "Default")
      (node (ref "IC1") (pin "52") (pinfunction "PC11_52") (pintype "bidirectional"))
      (node (ref "MSD") (pin "CS") (pinfunction "~{CS}/DAT3_CS") (pintype "bidirectional"))
      (node (ref "R10") (pin "1") (pinfunction "1_1") (pintype "passive"))
      (node (ref "SD") (pin "CS") (pinfunction "~{CS}/DAT3_CS") (pintype "bidirectional"))
    )
    (net (code "50") (name "SD_SCK") (class "Default")
      (node (ref "IC1") (pin "53") (pinfunction "PC12_53") (pintype "bidirectional"))
      (node (ref "MSD") (pin "SCK") (pinfunction "SCK_SCK") (pintype "bidirectional"))
      (node (ref "SD") (pin "SCK") (pinfunction "SCK_SCK") (pintype "bidirectional"))
    )
    (net (code "51") (name "SD_WP") (class "Default")
      (node (ref "IC1") (pin "24") (pinfunction "PC4_24") (pintype "bidirectional"))
      (node (ref "WP") (pin "1") (pinfunction "1_1") (pintype "passive"))
    )
    (net (code "52") (name "SPI_CS") (class "Default")
      (node (ref "IC1") (pin "50") (pinfunction "JTDI/PA15_50") (pintype "bidirectional"))
      (node (ref "J1") (pin "10") (pinfunction "10_10") (pintype "passive"))
      (node (ref "R8") (pin "1") (pinfunction "1_1") (pintype "passive"))
    )
    (net (code "53") (name "SPI_MISO{slash}UART_BUSY") (class "Default")
      (node (ref "IC1") (pin "22") (pinfunction "PA6_22") (pintype "bidirectional"))
      (node (ref "J1") (pin "7") (pinfunction "7_7") (pintype "passive"))
    )
    (net (code "54") (name "SPI_MOSI") (class "Default")
      (node (ref "IC1") (pin "23") (pinfunction "PA7_23") (pintype "bidirectional"))
      (node (ref "J1") (pin "8") (pinfunction "8_8") (pintype "passive"))
      (node (ref "R9") (pin "1") (pinfunction "1_1") (pintype "passive"))
    )
    (net (code "55") (name "SPI_SCK") (class "Default")
      (node (ref "IC1") (pin "55") (pinfunction "JTDO/PB3_55") (pintype "bidirectional"))
      (node (ref "J1") (pin "9") (pinfunction "9_9") (pintype "passive"))
    )
    (net (code "56") (name "SWCLK") (class "Default")
      (node (ref "IC1") (pin "49") (pinfunction "SWCLK/JTCK/PA14_49") (pintype "bidirectional"))
      (node (ref "SWD") (pin "SWCLK") (pinfunction "SWCLK_SWCLK") (pintype "bidirectional"))
    )
    (net (code "57") (name "SWDIO") (class "Default")
      (node (ref "IC1") (pin "46") (pinfunction "SWDIO/JTMS/PA13_46") (pintype "bidirectional"))
      (node (ref "SWD") (pin "SWDIO") (pinfunction "SWDIO_SWDIO") (pintype "bidirectional"))
    )
    (net (code "58") (name "UART_RX{slash}SPI_BUSY{slash}I2C_BUSY") (class "Default")
      (node (ref "IC1") (pin "43") (pinfunction "PA10_43") (pintype "bidirectional"))
      (node (ref "J1") (pin "4") (pinfunction "4_4") (pintype "passive"))
      (node (ref "R5") (pin "1") (pinfunction "1_1") (pintype "passive"))
    )
    (net (code "59") (name "UART_TX{slash}U1_CONNECT") (class "Default")
      (node (ref "IC1") (pin "42") (pinfunction "PA9_42") (pintype "bidirectional"))
      (node (ref "J1") (pin "3") (pinfunction "3_3") (pintype "passive"))
      (node (ref "R4") (pin "1") (pinfunction "1_1") (pintype "passive"))
    )
    (net (code "60") (name "USB0_N") (class "Default")
      (node (ref "IC1") (pin "44") (pinfunction "PA11_44") (pintype "bidirectional"))
      (node (ref "R16") (pin "1") (pinfunction "1_1") (pintype "passive"))
    )
    (net (code "61") (name "USB0_P") (class "Default")
      (node (ref "IC1") (pin "45") (pinfunction "PA12_45") (pintype "bidirectional"))
      (node (ref "R15") (pin "1") (pinfunction "1_1") (pintype "passive"))
    )
    (net (code "62") (name "USB1_N") (class "Default")
      (node (ref "IC1") (pin "35") (pinfunction "PB14_35") (pintype "bidirectional"))
      (node (ref "R18") (pin "1") (pinfunction "1_1") (pintype "passive"))
    )
    (net (code "63") (name "USB1_P") (class "Default")
      (node (ref "IC1") (pin "36") (pinfunction "PB15_36") (pintype "bidirectional"))
      (node (ref "R17") (pin "1") (pinfunction "1_1") (pintype "passive"))
    )
    (net (code "64") (name "VBAT") (class "Default")
      (node (ref "BAT") (pin "+") (pinfunction "VBAT_+") (pintype "power_in"))
      (node (ref "D2") (pin "A") (pinfunction "A_A") (pintype "passive"))
    )
    (net (code "65") (name "WAKEUP") (class "Default")
      (node (ref "IC1") (pin "14") (pinfunction "WKUP/PA0_14") (pintype "bidirectional"))
      (node (ref "J1") (pin "12") (pinfunction "12_12") (pintype "passive"))
    )
    (net (code "66") (name "unconnected-(FTDI-CTS-Pad2-CTS)") (class "Default")
      (node (ref "FTDI") (pin "2-CTS") (pinfunction "CTS_2-CTS") (pintype "bidirectional"))
    )
    (net (code "67") (name "unconnected-(FTDI-DTR-Pad6-DTR)") (class "Default")
      (node (ref "FTDI") (pin "6-DTR") (pinfunction "DTR_6-DTR") (pintype "bidirectional"))
    )
    (net (code "68") (name "unconnected-(IC1-JTRST{slash}PB4-Pad56)") (class "Default")
      (node (ref "IC1") (pin "56") (pinfunction "JTRST/PB4_56") (pintype "bidirectional"))
    )
    (net (code "69") (name "unconnected-(IC1-PA1-Pad15)") (class "Default")
      (node (ref "IC1") (pin "15") (pinfunction "PA1_15") (pintype "bidirectional"))
    )
    (net (code "70") (name "unconnected-(IC1-PA5-Pad21)") (class "Default")
      (node (ref "IC1") (pin "21") (pinfunction "PA5_21") (pintype "bidirectional"))
    )
    (net (code "71") (name "unconnected-(IC1-PA8-Pad41)") (class "Default")
      (node (ref "IC1") (pin "41") (pinfunction "PA8_41") (pintype "bidirectional"))
    )
    (net (code "72") (name "unconnected-(IC1-PB0-Pad26)") (class "Default")
      (node (ref "IC1") (pin "26") (pinfunction "PB0_26") (pintype "bidirectional"))
    )
    (net (code "73") (name "unconnected-(IC1-PB1-Pad27)") (class "Default")
      (node (ref "IC1") (pin "27") (pinfunction "PB1_27") (pintype "bidirectional"))
    )
    (net (code "74") (name "unconnected-(IC1-PB5-Pad57)") (class "Default")
      (node (ref "IC1") (pin "57") (pinfunction "PB5_57") (pintype "bidirectional"))
    )
    (net (code "75") (name "unconnected-(IC1-PB8-Pad61)") (class "Default")
      (node (ref "IC1") (pin "61") (pinfunction "PB8_61") (pintype "bidirectional"))
    )
    (net (code "76") (name "unconnected-(IC1-PB9-Pad62)") (class "Default")
      (node (ref "IC1") (pin "62") (pinfunction "PB9_62") (pintype "bidirectional"))
    )
    (net (code "77") (name "unconnected-(IC1-PB10-Pad29)") (class "Default")
      (node (ref "IC1") (pin "29") (pinfunction "PB10_29") (pintype "bidirectional"))
    )
    (net (code "78") (name "unconnected-(IC1-PB11-Pad30)") (class "Default")
      (node (ref "IC1") (pin "30") (pinfunction "PB11_30") (pintype "bidirectional"))
    )
    (net (code "79") (name "unconnected-(IC1-PB12-Pad33)") (class "Default")
      (node (ref "IC1") (pin "33") (pinfunction "PB12_33") (pintype "bidirectional"))
    )
    (net (code "80") (name "unconnected-(IC1-PB13-Pad34)") (class "Default")
      (node (ref "IC1") (pin "34") (pinfunction "PB13_34") (pintype "bidirectional"))
    )
    (net (code "81") (name "unconnected-(IC1-PC0-Pad8)") (class "Default")
      (node (ref "IC1") (pin "8") (pinfunction "PC0_8") (pintype "bidirectional"))
    )
    (net (code "82") (name "unconnected-(IC1-PC1-Pad9)") (class "Default")
      (node (ref "IC1") (pin "9") (pinfunction "PC1_9") (pintype "bidirectional"))
    )
    (net (code "83") (name "unconnected-(IC1-PC2-Pad10)") (class "Default")
      (node (ref "IC1") (pin "10") (pinfunction "PC2_10") (pintype "bidirectional"))
    )
    (net (code "84") (name "unconnected-(IC1-PC3-Pad11)") (class "Default")
      (node (ref "IC1") (pin "11") (pinfunction "PC3_11") (pintype "bidirectional"))
    )
    (net (code "85") (name "unconnected-(IC1-PC6-Pad37)") (class "Default")
      (node (ref "IC1") (pin "37") (pinfunction "PC6_37") (pintype "bidirectional"))
    )
    (net (code "86") (name "unconnected-(IC1-PC7-Pad38)") (class "Default")
      (node (ref "IC1") (pin "38") (pinfunction "PC7_38") (pintype "bidirectional"))
    )
    (net (code "87") (name "unconnected-(IC1-PC13-Pad2)") (class "Default")
      (node (ref "IC1") (pin "2") (pinfunction "PC13_2") (pintype "bidirectional"))
    )
  )
)
